# 150219_AriloRX_REV2_0_0.net
KiCad netlist of a schematic drawn in EAGLE
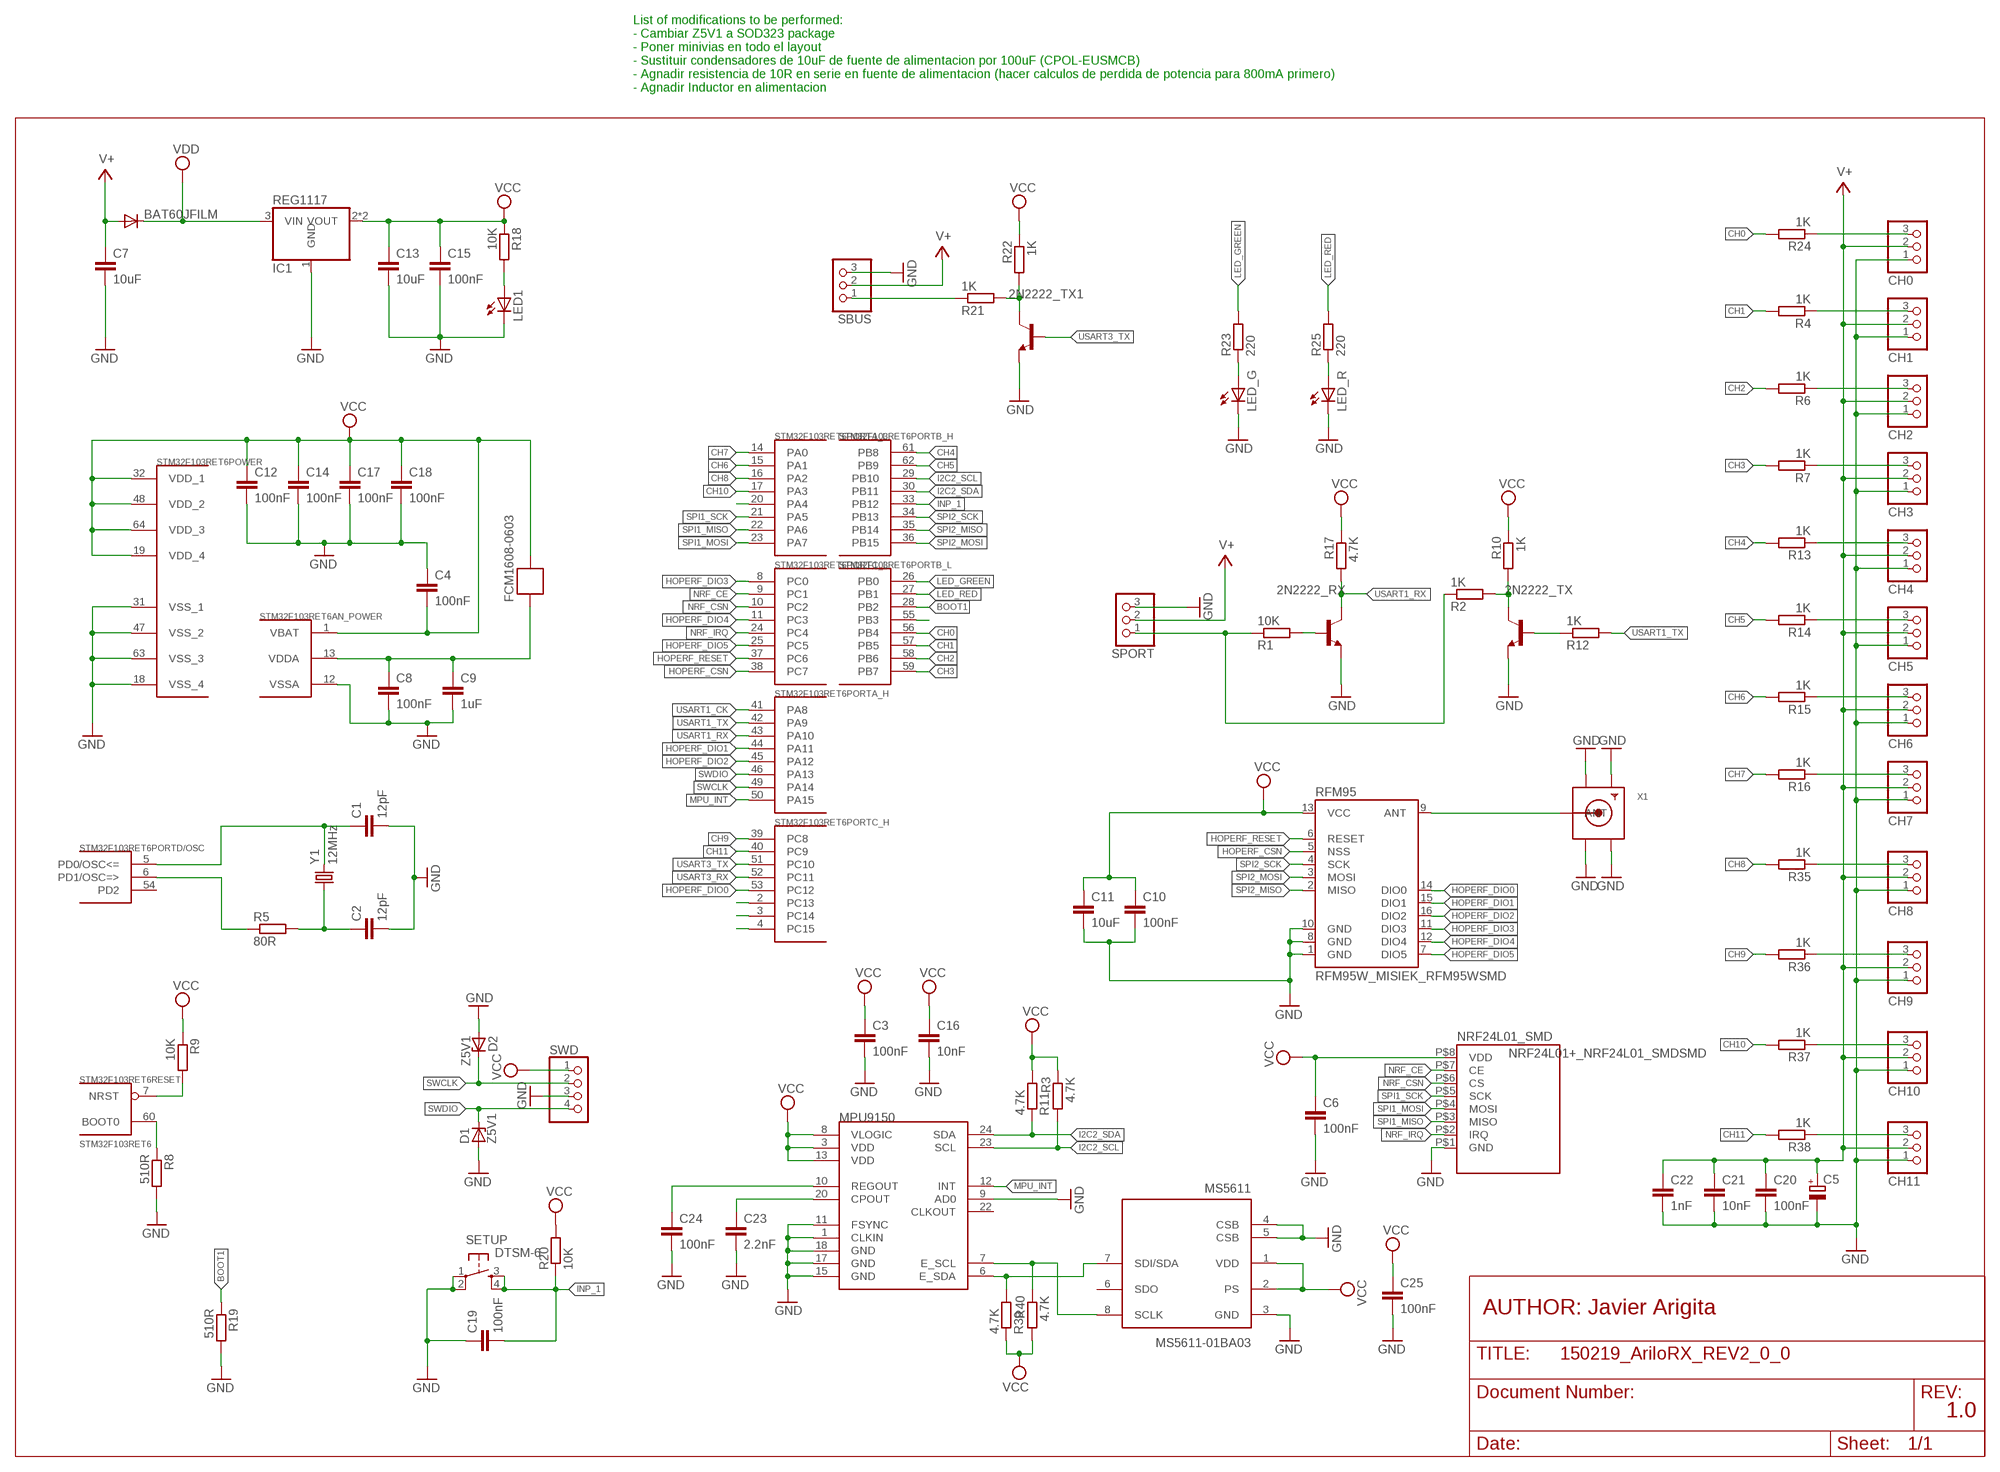
[diagram p0: schematic, sheet 1]

(export (version "E")
  (design (tool "Eeschema 10.0.6"))
  (components
    (comp (ref "2N2222_RX")
      (value "MMBT2222ALT1-NPN-SOT23-BEC")
      (footprint "eagle-import:SOT23-BEC")
      (libsource (lib "eagle-import") (part "-NPN-SOT23-BECMMBT2222ALT1"))
    )
    (comp (ref "2N2222_TX")
      (value "MMBT2222ALT1-NPN-SOT23-BEC")
      (footprint "eagle-import:SOT23-BEC")
      (libsource (lib "eagle-import") (part "-NPN-SOT23-BECMMBT2222ALT1"))
    )
    (comp (ref "2N2222_TX1")
      (value "MMBT2222ALT1-NPN-SOT23-BEC")
      (footprint "eagle-import:SOT23-BEC")
      (libsource (lib "eagle-import") (part "-NPN-SOT23-BECMMBT2222ALT1"))
    )
    (comp (ref "BAT60JFILM")
      (value "DIODE-SOD323-R")
      (footprint "eagle-import:SOD323-R")
      (libsource (lib "eagle-import") (part "DIODE-SOD323-R"))
    )
    (comp (ref "C1")
      (value "12pF")
      (footprint "eagle-import:RESISTOR_C0603")
      (libsource (lib "eagle-import") (part "RESISTOR_C-EUC0603"))
    )
    (comp (ref "C2")
      (value "12pF")
      (footprint "eagle-import:RESISTOR_C0603")
      (libsource (lib "eagle-import") (part "RESISTOR_C-EUC0603"))
    )
    (comp (ref "C3")
      (value "100nF")
      (footprint "eagle-import:RESISTOR_C0603")
      (libsource (lib "eagle-import") (part "RESISTOR_C-EUC0603"))
    )
    (comp (ref "C4")
      (value "100nF")
      (footprint "eagle-import:RESISTOR_C0603")
      (libsource (lib "eagle-import") (part "RESISTOR_C-EUC0603"))
    )
    (comp (ref "C5")
      (value "CPOL-EUSMCB")
      (footprint "eagle-import:SMC_B")
      (libsource (lib "eagle-import") (part "CPOL-EUSMCB"))
    )
    (comp (ref "C6")
      (value "100nF")
      (footprint "eagle-import:RESISTOR_C0603")
      (libsource (lib "eagle-import") (part "RESISTOR_C-EUC0603"))
    )
    (comp (ref "C7")
      (value "10uF")
      (footprint "eagle-import:RESISTOR_C3216")
      (libsource (lib "eagle-import") (part "RESISTOR_C-EUC3216"))
    )
    (comp (ref "C8")
      (value "100nF")
      (footprint "eagle-import:RESISTOR_C0603")
      (libsource (lib "eagle-import") (part "RESISTOR_C-EUC0603"))
    )
    (comp (ref "C9")
      (value "1uF")
      (footprint "eagle-import:RESISTOR_C0603")
      (libsource (lib "eagle-import") (part "RESISTOR_C-EUC0603"))
    )
    (comp (ref "C10")
      (value "100nF")
      (footprint "eagle-import:RESISTOR_C0603")
      (libsource (lib "eagle-import") (part "RESISTOR_C-EUC0603"))
    )
    (comp (ref "C11")
      (value "10uF")
      (footprint "eagle-import:RESISTOR_C3216")
      (libsource (lib "eagle-import") (part "RESISTOR_C-EUC3216"))
    )
    (comp (ref "C12")
      (value "100nF")
      (footprint "eagle-import:RESISTOR_C0603")
      (libsource (lib "eagle-import") (part "RESISTOR_C-EUC0603"))
    )
    (comp (ref "C13")
      (value "10uF")
      (footprint "eagle-import:RESISTOR_C3216")
      (libsource (lib "eagle-import") (part "RESISTOR_C-EUC3216"))
    )
    (comp (ref "C14")
      (value "100nF")
      (footprint "eagle-import:RESISTOR_C0603")
      (libsource (lib "eagle-import") (part "RESISTOR_C-EUC0603"))
    )
    (comp (ref "C15")
      (value "100nF")
      (footprint "eagle-import:RESISTOR_C0603")
      (libsource (lib "eagle-import") (part "RESISTOR_C-EUC0603"))
    )
    (comp (ref "C16")
      (value "10nF")
      (footprint "eagle-import:RESISTOR_C0603")
      (libsource (lib "eagle-import") (part "RESISTOR_C-EUC0603"))
    )
    (comp (ref "C17")
      (value "100nF")
      (footprint "eagle-import:RESISTOR_C0603")
      (libsource (lib "eagle-import") (part "RESISTOR_C-EUC0603"))
    )
    (comp (ref "C18")
      (value "100nF")
      (footprint "eagle-import:RESISTOR_C0603")
      (libsource (lib "eagle-import") (part "RESISTOR_C-EUC0603"))
    )
    (comp (ref "C19")
      (value "100nF")
      (footprint "eagle-import:RESISTOR_C0603")
      (libsource (lib "eagle-import") (part "RESISTOR_C-EUC0603"))
    )
    (comp (ref "C20")
      (value "100nF")
      (footprint "eagle-import:RESISTOR_C0603")
      (libsource (lib "eagle-import") (part "RESISTOR_C-EUC0603"))
    )
    (comp (ref "C21")
      (value "10nF")
      (footprint "eagle-import:RESISTOR_C0603")
      (libsource (lib "eagle-import") (part "RESISTOR_C-EUC0603"))
    )
    (comp (ref "C22")
      (value "1nF")
      (footprint "eagle-import:RESISTOR_C0603")
      (libsource (lib "eagle-import") (part "RESISTOR_C-EUC0603"))
    )
    (comp (ref "C23")
      (value "2.2nF")
      (footprint "eagle-import:RESISTOR_C0603")
      (libsource (lib "eagle-import") (part "RESISTOR_C-EUC0603"))
    )
    (comp (ref "C24")
      (value "100nF")
      (footprint "eagle-import:RESISTOR_C0603")
      (libsource (lib "eagle-import") (part "RESISTOR_C-EUC0603"))
    )
    (comp (ref "C25")
      (value "100nF")
      (footprint "eagle-import:RESISTOR_C0603")
      (libsource (lib "eagle-import") (part "RESISTOR_C-EUC0603"))
    )
    (comp (ref "CH0")
      (value "PINHD-1X3")
      (footprint "eagle-import:1X03")
      (libsource (lib "eagle-import") (part "PINHD-1X3"))
    )
    (comp (ref "CH1")
      (value "PINHD-1X3")
      (footprint "eagle-import:1X03")
      (libsource (lib "eagle-import") (part "PINHD-1X3"))
    )
    (comp (ref "CH2")
      (value "PINHD-1X3")
      (footprint "eagle-import:1X03")
      (libsource (lib "eagle-import") (part "PINHD-1X3"))
    )
    (comp (ref "CH3")
      (value "PINHD-1X3")
      (footprint "eagle-import:1X03")
      (libsource (lib "eagle-import") (part "PINHD-1X3"))
    )
    (comp (ref "CH4")
      (value "PINHD-1X3")
      (footprint "eagle-import:1X03")
      (libsource (lib "eagle-import") (part "PINHD-1X3"))
    )
    (comp (ref "CH5")
      (value "PINHD-1X3")
      (footprint "eagle-import:1X03")
      (libsource (lib "eagle-import") (part "PINHD-1X3"))
    )
    (comp (ref "CH6")
      (value "PINHD-1X3")
      (footprint "eagle-import:1X03")
      (libsource (lib "eagle-import") (part "PINHD-1X3"))
    )
    (comp (ref "CH7")
      (value "PINHD-1X3")
      (footprint "eagle-import:1X03")
      (libsource (lib "eagle-import") (part "PINHD-1X3"))
    )
    (comp (ref "CH8")
      (value "PINHD-1X3")
      (footprint "eagle-import:1X03")
      (libsource (lib "eagle-import") (part "PINHD-1X3"))
    )
    (comp (ref "CH9")
      (value "PINHD-1X3")
      (footprint "eagle-import:1X03")
      (libsource (lib "eagle-import") (part "PINHD-1X3"))
    )
    (comp (ref "CH10")
      (value "PINHD-1X3")
      (footprint "eagle-import:1X03")
      (libsource (lib "eagle-import") (part "PINHD-1X3"))
    )
    (comp (ref "CH11")
      (value "PINHD-1X3")
      (footprint "eagle-import:1X03")
      (libsource (lib "eagle-import") (part "PINHD-1X3"))
    )
    (comp (ref "D1")
      (value "Z5V1")
      (footprint "eagle-import:SOD80C")
      (libsource (lib "eagle-import") (part "ZENER-DIODESOD80C"))
    )
    (comp (ref "D2")
      (value "Z5V1")
      (footprint "eagle-import:SOD80C")
      (libsource (lib "eagle-import") (part "ZENER-DIODESOD80C"))
    )
    (comp (ref "FCM1608-0603")
      (value "FERRITE-BEAD")
      (footprint "eagle-import:R0603")
      (libsource (lib "eagle-import") (part "FERRITE-BEAD"))
    )
    (comp (ref "IC1")
      (value "REG1117")
      (footprint "eagle-import:SOT223")
      (libsource (lib "eagle-import") (part "REG1117"))
    )
    (comp (ref "LED1")
      (value "LED_LEDCHIP-LED0603")
      (footprint "eagle-import:LED_CHIP-LED0603")
      (libsource (lib "eagle-import") (part "LED_LEDCHIP-LED0603"))
    )
    (comp (ref "LED_G")
      (value "LEDCHIP-LED0603")
      (footprint "eagle-import:CHIP-LED0603")
      (libsource (lib "eagle-import") (part "LEDCHIP-LED0603"))
    )
    (comp (ref "LED_R")
      (value "LEDCHIP-LED0603")
      (footprint "eagle-import:CHIP-LED0603")
      (libsource (lib "eagle-import") (part "LEDCHIP-LED0603"))
    )
    (comp (ref "MPU9150")
      (value "MPU-9150QFN-24-NP")
      (footprint "eagle-import:QFN-24-NP")
      (libsource (lib "eagle-import") (part "MPU-9150QFN-24-NP"))
    )
    (comp (ref "MS5611")
      (value "MS5611-01BA03")
      (footprint "eagle-import:SON125P300X500X100-8N")
      (libsource (lib "eagle-import") (part "MS5611-01BA03"))
    )
    (comp (ref "NRF24L01_SMD")
      (value "NRF24L01+_NRF24L01_SMDSMD")
      (footprint "eagle-import:NRF24L01+_NRF24L01_SMD")
      (libsource (lib "eagle-import") (part "NRF24L01+_NRF24L01_SMDSMD"))
    )
    (comp (ref "R1")
      (value "10K")
      (footprint "eagle-import:RCL_R0603")
      (libsource (lib "eagle-import") (part "RCL_R-EU_R0603"))
    )
    (comp (ref "R2")
      (value "1K")
      (footprint "eagle-import:RCL_R0603")
      (libsource (lib "eagle-import") (part "RCL_R-EU_R0603"))
    )
    (comp (ref "R3")
      (value "4.7K")
      (footprint "eagle-import:RCL_R0603")
      (libsource (lib "eagle-import") (part "RCL_R-EU_R0603"))
    )
    (comp (ref "R4")
      (value "1K")
      (footprint "eagle-import:RCL_R0603")
      (libsource (lib "eagle-import") (part "RCL_R-EU_R0603"))
    )
    (comp (ref "R5")
      (value "80R")
      (footprint "eagle-import:RCL_R0603")
      (libsource (lib "eagle-import") (part "RCL_R-EU_R0603"))
    )
    (comp (ref "R6")
      (value "1K")
      (footprint "eagle-import:RCL_R0603")
      (libsource (lib "eagle-import") (part "RCL_R-EU_R0603"))
    )
    (comp (ref "R7")
      (value "1K")
      (footprint "eagle-import:RCL_R0603")
      (libsource (lib "eagle-import") (part "RCL_R-EU_R0603"))
    )
    (comp (ref "R8")
      (value "510R")
      (footprint "eagle-import:RCL_R0603")
      (libsource (lib "eagle-import") (part "RCL_R-EU_R0603"))
    )
    (comp (ref "R9")
      (value "10K")
      (footprint "eagle-import:RCL_R0603")
      (libsource (lib "eagle-import") (part "RCL_R-EU_R0603"))
    )
    (comp (ref "R10")
      (value "1K")
      (footprint "eagle-import:RCL_R0603")
      (libsource (lib "eagle-import") (part "RCL_R-EU_R0603"))
    )
    (comp (ref "R11")
      (value "4.7K")
      (footprint "eagle-import:RCL_R0603")
      (libsource (lib "eagle-import") (part "RCL_R-EU_R0603"))
    )
    (comp (ref "R12")
      (value "1K")
      (footprint "eagle-import:RCL_R0603")
      (libsource (lib "eagle-import") (part "RCL_R-EU_R0603"))
    )
    (comp (ref "R13")
      (value "1K")
      (footprint "eagle-import:RCL_R0603")
      (libsource (lib "eagle-import") (part "RCL_R-EU_R0603"))
    )
    (comp (ref "R14")
      (value "1K")
      (footprint "eagle-import:RCL_R0603")
      (libsource (lib "eagle-import") (part "RCL_R-EU_R0603"))
    )
    (comp (ref "R15")
      (value "1K")
      (footprint "eagle-import:RCL_R0603")
      (libsource (lib "eagle-import") (part "RCL_R-EU_R0603"))
    )
    (comp (ref "R16")
      (value "1K")
      (footprint "eagle-import:RCL_R0603")
      (libsource (lib "eagle-import") (part "RCL_R-EU_R0603"))
    )
    (comp (ref "R17")
      (value "4.7K")
      (footprint "eagle-import:RCL_R0603")
      (libsource (lib "eagle-import") (part "RCL_R-EU_R0603"))
    )
    (comp (ref "R18")
      (value "10K")
      (footprint "eagle-import:RCL_R0603")
      (libsource (lib "eagle-import") (part "RCL_R-EU_R0603"))
    )
    (comp (ref "R19")
      (value "510R")
      (footprint "eagle-import:RCL_R0603")
      (libsource (lib "eagle-import") (part "RCL_R-EU_R0603"))
    )
    (comp (ref "R20")
      (value "10K")
      (footprint "eagle-import:RCL_R0603")
      (libsource (lib "eagle-import") (part "RCL_R-EU_R0603"))
    )
    (comp (ref "R21")
      (value "1K")
      (footprint "eagle-import:RCL_R0603")
      (libsource (lib "eagle-import") (part "RCL_R-EU_R0603"))
    )
    (comp (ref "R22")
      (value "1K")
      (footprint "eagle-import:RCL_R0603")
      (libsource (lib "eagle-import") (part "RCL_R-EU_R0603"))
    )
    (comp (ref "R23")
      (value "220")
      (footprint "eagle-import:RCL_R0603")
      (libsource (lib "eagle-import") (part "RCL_R-EU_R0603"))
    )
    (comp (ref "R24")
      (value "1K")
      (footprint "eagle-import:RCL_R0603")
      (libsource (lib "eagle-import") (part "RCL_R-EU_R0603"))
    )
    (comp (ref "R25")
      (value "220")
      (footprint "eagle-import:RCL_R0603")
      (libsource (lib "eagle-import") (part "RCL_R-EU_R0603"))
    )
    (comp (ref "R35")
      (value "1K")
      (footprint "eagle-import:RCL_R0603")
      (libsource (lib "eagle-import") (part "RCL_R-EU_R0603"))
    )
    (comp (ref "R36")
      (value "1K")
      (footprint "eagle-import:RCL_R0603")
      (libsource (lib "eagle-import") (part "RCL_R-EU_R0603"))
    )
    (comp (ref "R37")
      (value "1K")
      (footprint "eagle-import:RCL_R0603")
      (libsource (lib "eagle-import") (part "RCL_R-EU_R0603"))
    )
    (comp (ref "R38")
      (value "1K")
      (footprint "eagle-import:RCL_R0603")
      (libsource (lib "eagle-import") (part "RCL_R-EU_R0603"))
    )
    (comp (ref "R39")
      (value "4.7K")
      (footprint "eagle-import:RCL_R0603")
      (libsource (lib "eagle-import") (part "RCL_R-EU_R0603"))
    )
    (comp (ref "R40")
      (value "4.7K")
      (footprint "eagle-import:RCL_R0603")
      (libsource (lib "eagle-import") (part "RCL_R-EU_R0603"))
    )
    (comp (ref "RFM95")
      (value "RFM95W_MISIEK_RFM95WSMD")
      (footprint "eagle-import:RFM95W_MISIEK_RFM95W_SMD")
      (libsource (lib "eagle-import") (part "RFM95W_MISIEK_RFM95WSMD"))
    )
    (comp (ref "SBUS")
      (value "PINHD-1X3")
      (footprint "eagle-import:1X03")
      (libsource (lib "eagle-import") (part "PINHD-1X3"))
    )
    (comp (ref "SETUP")
      (value "DTSM-6")
      (footprint "eagle-import:DTSM-6")
      (libsource (lib "eagle-import") (part "DTSM-6"))
    )
    (comp (ref "SPORT")
      (value "PINHD-1X3")
      (footprint "eagle-import:1X03")
      (libsource (lib "eagle-import") (part "PINHD-1X3"))
    )
    (comp (ref "STM32F103RET6")
      (value "STM32F103RET6")
      (footprint "eagle-import:TQFP64")
      (libsource (lib "eagle-import") (part "STM32F10XRXT6"))
    )
    (comp (ref "SWD")
      (value "PINHD-1X4")
      (footprint "eagle-import:1X04")
      (libsource (lib "eagle-import") (part "PINHD-1X4"))
    )
    (comp (ref "X1")
      (value "SMACONNECTOR_EDGE")
      (footprint "eagle-import:SMA_EDGELAUNCH")
      (libsource (lib "eagle-import") (part "SMACONNECTOR_EDGE"))
    )
    (comp (ref "Y1")
      (value "12MHz")
      (footprint "eagle-import:CRYSTAL-SMD-5X3")
      (libsource (lib "eagle-import") (part "CRYSTAL5X3"))
    )
  )
  (nets
    (net (code "1") (name "BOOT1") (class "Default")
      (node (ref "R19") (pin "1") (pinfunction "1_1") (pintype "passive"))
      (node (ref "STM32F103RET6") (pin "28") (pinfunction "PB2_28") (pintype "bidirectional"))
    )
    (net (code "2") (name "CH0") (class "Default")
      (node (ref "R24") (pin "2") (pinfunction "2_2") (pintype "passive"))
      (node (ref "STM32F103RET6") (pin "56") (pinfunction "PB4_56") (pintype "bidirectional"))
    )
    (net (code "3") (name "CH1") (class "Default")
      (node (ref "R4") (pin "2") (pinfunction "2_2") (pintype "passive"))
      (node (ref "STM32F103RET6") (pin "57") (pinfunction "PB5_57") (pintype "bidirectional"))
    )
    (net (code "4") (name "CH2") (class "Default")
      (node (ref "R6") (pin "2") (pinfunction "2_2") (pintype "passive"))
      (node (ref "STM32F103RET6") (pin "58") (pinfunction "PB6_58") (pintype "bidirectional"))
    )
    (net (code "5") (name "CH3") (class "Default")
      (node (ref "R7") (pin "2") (pinfunction "2_2") (pintype "passive"))
      (node (ref "STM32F103RET6") (pin "59") (pinfunction "PB7_59") (pintype "bidirectional"))
    )
    (net (code "6") (name "CH4") (class "Default")
      (node (ref "R13") (pin "2") (pinfunction "2_2") (pintype "passive"))
      (node (ref "STM32F103RET6") (pin "61") (pinfunction "PB8_61") (pintype "bidirectional"))
    )
    (net (code "7") (name "CH5") (class "Default")
      (node (ref "R14") (pin "2") (pinfunction "2_2") (pintype "passive"))
      (node (ref "STM32F103RET6") (pin "62") (pinfunction "PB9_62") (pintype "bidirectional"))
    )
    (net (code "8") (name "CH6") (class "Default")
      (node (ref "R15") (pin "2") (pinfunction "2_2") (pintype "passive"))
      (node (ref "STM32F103RET6") (pin "15") (pinfunction "PA1_15") (pintype "bidirectional"))
    )
    (net (code "9") (name "CH7") (class "Default")
      (node (ref "R16") (pin "2") (pinfunction "2_2") (pintype "passive"))
      (node (ref "STM32F103RET6") (pin "14") (pinfunction "PA0_14") (pintype "bidirectional"))
    )
    (net (code "10") (name "CH8") (class "Default")
      (node (ref "R35") (pin "2") (pinfunction "2_2") (pintype "passive"))
      (node (ref "STM32F103RET6") (pin "16") (pinfunction "PA2_16") (pintype "bidirectional"))
    )
    (net (code "11") (name "CH9") (class "Default")
      (node (ref "R36") (pin "2") (pinfunction "2_2") (pintype "passive"))
      (node (ref "STM32F103RET6") (pin "39") (pinfunction "PC8_39") (pintype "bidirectional"))
    )
    (net (code "12") (name "CH10") (class "Default")
      (node (ref "R37") (pin "2") (pinfunction "2_2") (pintype "passive"))
      (node (ref "STM32F103RET6") (pin "17") (pinfunction "PA3_17") (pintype "bidirectional"))
    )
    (net (code "13") (name "CH11") (class "Default")
      (node (ref "R38") (pin "2") (pinfunction "2_2") (pintype "passive"))
      (node (ref "STM32F103RET6") (pin "40") (pinfunction "PC9_40") (pintype "bidirectional"))
    )
    (net (code "14") (name "GND") (class "Default")
      (node (ref "2N2222_RX") (pin "E") (pinfunction "E_E") (pintype "passive"))
      (node (ref "2N2222_TX") (pin "E") (pinfunction "E_E") (pintype "passive"))
      (node (ref "2N2222_TX1") (pin "E") (pinfunction "E_E") (pintype "passive"))
      (node (ref "C1") (pin "2") (pinfunction "2_2") (pintype "passive"))
      (node (ref "C10") (pin "2") (pinfunction "2_2") (pintype "passive"))
      (node (ref "C11") (pin "2") (pinfunction "2_2") (pintype "passive"))
      (node (ref "C12") (pin "2") (pinfunction "2_2") (pintype "passive"))
      (node (ref "C13") (pin "2") (pinfunction "2_2") (pintype "passive"))
      (node (ref "C14") (pin "2") (pinfunction "2_2") (pintype "passive"))
      (node (ref "C15") (pin "2") (pinfunction "2_2") (pintype "passive"))
      (node (ref "C16") (pin "2") (pinfunction "2_2") (pintype "passive"))
      (node (ref "C17") (pin "2") (pinfunction "2_2") (pintype "passive"))
      (node (ref "C18") (pin "2") (pinfunction "2_2") (pintype "passive"))
      (node (ref "C19") (pin "1") (pinfunction "1_1") (pintype "passive"))
      (node (ref "C2") (pin "2") (pinfunction "2_2") (pintype "passive"))
      (node (ref "C20") (pin "2") (pinfunction "2_2") (pintype "passive"))
      (node (ref "C21") (pin "2") (pinfunction "2_2") (pintype "passive"))
      (node (ref "C22") (pin "2") (pinfunction "2_2") (pintype "passive"))
      (node (ref "C23") (pin "2") (pinfunction "2_2") (pintype "passive"))
      (node (ref "C24") (pin "2") (pinfunction "2_2") (pintype "passive"))
      (node (ref "C25") (pin "2") (pinfunction "2_2") (pintype "passive"))
      (node (ref "C3") (pin "2") (pinfunction "2_2") (pintype "passive"))
      (node (ref "C4") (pin "1") (pinfunction "1_1") (pintype "passive"))
      (node (ref "C5") (pin "-") (pinfunction "-_-") (pintype "passive"))
      (node (ref "C6") (pin "2") (pinfunction "2_2") (pintype "passive"))
      (node (ref "C7") (pin "2") (pinfunction "2_2") (pintype "passive"))
      (node (ref "C8") (pin "2") (pinfunction "2_2") (pintype "passive"))
      (node (ref "C9") (pin "2") (pinfunction "2_2") (pintype "passive"))
      (node (ref "CH0") (pin "1") (pinfunction "1_1") (pintype "passive"))
      (node (ref "CH1") (pin "1") (pinfunction "1_1") (pintype "passive"))
      (node (ref "CH10") (pin "1") (pinfunction "1_1") (pintype "passive"))
      (node (ref "CH11") (pin "1") (pinfunction "1_1") (pintype "passive"))
      (node (ref "CH2") (pin "1") (pinfunction "1_1") (pintype "passive"))
      (node (ref "CH3") (pin "1") (pinfunction "1_1") (pintype "passive"))
      (node (ref "CH4") (pin "1") (pinfunction "1_1") (pintype "passive"))
      (node (ref "CH5") (pin "1") (pinfunction "1_1") (pintype "passive"))
      (node (ref "CH6") (pin "1") (pinfunction "1_1") (pintype "passive"))
      (node (ref "CH7") (pin "1") (pinfunction "1_1") (pintype "passive"))
      (node (ref "CH8") (pin "1") (pinfunction "1_1") (pintype "passive"))
      (node (ref "CH9") (pin "1") (pinfunction "1_1") (pintype "passive"))
      (node (ref "D1") (pin "A") (pinfunction "A_A") (pintype "passive"))
      (node (ref "D2") (pin "A") (pinfunction "A_A") (pintype "passive"))
      (node (ref "IC1") (pin "1") (pinfunction "GND_1") (pintype "power_in"))
      (node (ref "LED1") (pin "C") (pinfunction "C_C") (pintype "passive"))
      (node (ref "LED_G") (pin "C") (pinfunction "C_C") (pintype "passive"))
      (node (ref "LED_R") (pin "C") (pinfunction "C_C") (pintype "passive"))
      (node (ref "MPU9150") (pin "1") (pinfunction "CLKIN_1") (pintype "bidirectional"))
      (node (ref "MPU9150") (pin "11") (pinfunction "FSYNC_11") (pintype "bidirectional"))
      (node (ref "MPU9150") (pin "15") (pinfunction "GND_15") (pintype "bidirectional"))
      (node (ref "MPU9150") (pin "17") (pinfunction "GND_17") (pintype "bidirectional"))
      (node (ref "MPU9150") (pin "18") (pinfunction "GND_18") (pintype "bidirectional"))
      (node (ref "MPU9150") (pin "9") (pinfunction "AD0_9") (pintype "bidirectional"))
      (node (ref "MS5611") (pin "3") (pinfunction "GND_3") (pintype "power_in"))
      (node (ref "MS5611") (pin "4") (pinfunction "CSB_4") (pintype "input"))
      (node (ref "MS5611") (pin "5") (pinfunction "CSB_5") (pintype "input"))
      (node (ref "NRF24L01_SMD") (pin "P$1") (pinfunction "GND_P$1") (pintype "power_in"))
      (node (ref "R19") (pin "2") (pinfunction "2_2") (pintype "passive"))
      (node (ref "R8") (pin "2") (pinfunction "2_2") (pintype "passive"))
      (node (ref "RFM95") (pin "1") (pinfunction "GND_1") (pintype "power_in"))
      (node (ref "RFM95") (pin "10") (pinfunction "GND_10") (pintype "power_in"))
      (node (ref "RFM95") (pin "8") (pinfunction "GND_8") (pintype "power_in"))
      (node (ref "SBUS") (pin "3") (pinfunction "3_3") (pintype "passive"))
      (node (ref "SETUP") (pin "1") (pinfunction "1_1") (pintype "passive"))
      (node (ref "SETUP") (pin "2") (pinfunction "2_2") (pintype "passive"))
      (node (ref "SPORT") (pin "3") (pinfunction "3_3") (pintype "passive"))
      (node (ref "STM32F103RET6") (pin "12") (pinfunction "VSSA_12") (pintype "power_in"))
      (node (ref "STM32F103RET6") (pin "18") (pinfunction "VSS_4_18") (pintype "power_in"))
      (node (ref "STM32F103RET6") (pin "31") (pinfunction "VSS_1_31") (pintype "power_in"))
      (node (ref "STM32F103RET6") (pin "47") (pinfunction "VSS_2_47") (pintype "power_in"))
      (node (ref "STM32F103RET6") (pin "63") (pinfunction "VSS_3_63") (pintype "power_in"))
      (node (ref "SWD") (pin "3") (pinfunction "3_3") (pintype "passive"))
      (node (ref "X1") (pin "GND@1") (pinfunction "GND4_GND@1") (pintype "power_in"))
      (node (ref "X1") (pin "GND@2") (pinfunction "GND3_GND@2") (pintype "power_in"))
      (node (ref "X1") (pin "GND@3") (pinfunction "GND2_GND@3") (pintype "power_in"))
      (node (ref "X1") (pin "GND@4") (pinfunction "GND1_GND@4") (pintype "power_in"))
    )
    (net (code "15") (name "HOPERF_CSN") (class "Default")
      (node (ref "RFM95") (pin "5") (pinfunction "NSS_5") (pintype "input"))
      (node (ref "STM32F103RET6") (pin "38") (pinfunction "PC7_38") (pintype "bidirectional"))
    )
    (net (code "16") (name "HOPERF_DIO0") (class "Default")
      (node (ref "RFM95") (pin "14") (pinfunction "DIO0_14") (pintype "input"))
      (node (ref "STM32F103RET6") (pin "53") (pinfunction "PC12_53") (pintype "bidirectional"))
    )
    (net (code "17") (name "HOPERF_DIO1") (class "Default")
      (node (ref "RFM95") (pin "15") (pinfunction "DIO1_15") (pintype "input"))
      (node (ref "STM32F103RET6") (pin "44") (pinfunction "PA11_44") (pintype "bidirectional"))
    )
    (net (code "18") (name "HOPERF_DIO2") (class "Default")
      (node (ref "RFM95") (pin "16") (pinfunction "DIO2_16") (pintype "input"))
      (node (ref "STM32F103RET6") (pin "45") (pinfunction "PA12_45") (pintype "bidirectional"))
    )
    (net (code "19") (name "HOPERF_DIO3") (class "Default")
      (node (ref "RFM95") (pin "11") (pinfunction "DIO3_11") (pintype "bidirectional"))
      (node (ref "STM32F103RET6") (pin "8") (pinfunction "PC0_8") (pintype "bidirectional"))
    )
    (net (code "20") (name "HOPERF_DIO4") (class "Default")
      (node (ref "RFM95") (pin "12") (pinfunction "DIO4_12") (pintype "bidirectional"))
      (node (ref "STM32F103RET6") (pin "11") (pinfunction "PC3_11") (pintype "bidirectional"))
    )
    (net (code "21") (name "HOPERF_DIO5") (class "Default")
      (node (ref "RFM95") (pin "7") (pinfunction "DIO5_7") (pintype "bidirectional"))
      (node (ref "STM32F103RET6") (pin "25") (pinfunction "PC5_25") (pintype "bidirectional"))
    )
    (net (code "22") (name "HOPERF_RESET") (class "Default")
      (node (ref "RFM95") (pin "6") (pinfunction "RESET_6") (pintype "output"))
      (node (ref "STM32F103RET6") (pin "37") (pinfunction "PC6_37") (pintype "bidirectional"))
    )
    (net (code "23") (name "I2C2_SCL") (class "Default")
      (node (ref "MPU9150") (pin "23") (pinfunction "SCL_23") (pintype "bidirectional"))
      (node (ref "R3") (pin "2") (pinfunction "2_2") (pintype "passive"))
      (node (ref "STM32F103RET6") (pin "29") (pinfunction "PB10_29") (pintype "bidirectional"))
    )
    (net (code "24") (name "I2C2_SDA") (class "Default")
      (node (ref "MPU9150") (pin "24") (pinfunction "SDA_24") (pintype "bidirectional"))
      (node (ref "R11") (pin "1") (pinfunction "1_1") (pintype "passive"))
      (node (ref "STM32F103RET6") (pin "30") (pinfunction "PB11_30") (pintype "bidirectional"))
    )
    (net (code "25") (name "INP_1") (class "Default")
      (node (ref "C19") (pin "2") (pinfunction "2_2") (pintype "passive"))
      (node (ref "R20") (pin "1") (pinfunction "1_1") (pintype "passive"))
      (node (ref "SETUP") (pin "3") (pinfunction "3_3") (pintype "passive"))
      (node (ref "SETUP") (pin "4") (pinfunction "4_4") (pintype "passive"))
      (node (ref "STM32F103RET6") (pin "33") (pinfunction "PB12_33") (pintype "bidirectional"))
    )
    (net (code "26") (name "LED_GREEN") (class "Default")
      (node (ref "R23") (pin "2") (pinfunction "2_2") (pintype "passive"))
      (node (ref "STM32F103RET6") (pin "26") (pinfunction "PB0_26") (pintype "bidirectional"))
    )
    (net (code "27") (name "LED_RED") (class "Default")
      (node (ref "R25") (pin "2") (pinfunction "2_2") (pintype "passive"))
      (node (ref "STM32F103RET6") (pin "27") (pinfunction "PB1_27") (pintype "bidirectional"))
    )
    (net (code "28") (name "MPU_INT") (class "Default")
      (node (ref "MPU9150") (pin "12") (pinfunction "INT_12") (pintype "bidirectional"))
      (node (ref "STM32F103RET6") (pin "50") (pinfunction "PA15_50") (pintype "bidirectional"))
    )
    (net (code "29") (name "NRF_CE") (class "Default")
      (node (ref "NRF24L01_SMD") (pin "P$7") (pinfunction "CE_P$7") (pintype "input"))
      (node (ref "STM32F103RET6") (pin "9") (pinfunction "PC1_9") (pintype "bidirectional"))
    )
    (net (code "30") (name "NRF_CSN") (class "Default")
      (node (ref "NRF24L01_SMD") (pin "P$6") (pinfunction "CS_P$6") (pintype "input"))
      (node (ref "STM32F103RET6") (pin "10") (pinfunction "PC2_10") (pintype "bidirectional"))
    )
    (net (code "31") (name "NRF_IRQ") (class "Default")
      (node (ref "NRF24L01_SMD") (pin "P$2") (pinfunction "IRQ_P$2") (pintype "output"))
      (node (ref "STM32F103RET6") (pin "24") (pinfunction "PC4_24") (pintype "bidirectional"))
    )
    (net (code "32") (name "Net-(2N2222_RX-PadB)") (class "Default")
      (node (ref "2N2222_RX") (pin "B") (pinfunction "B_B") (pintype "passive"))
      (node (ref "R1") (pin "2") (pinfunction "2_2") (pintype "passive"))
    )
    (net (code "33") (name "Net-(2N2222_TX-PadB)") (class "Default")
      (node (ref "2N2222_TX") (pin "B") (pinfunction "B_B") (pintype "passive"))
      (node (ref "R12") (pin "1") (pinfunction "1_1") (pintype "passive"))
    )
    (net (code "34") (name "Net-(2N2222_TX-PadC)") (class "Default")
      (node (ref "2N2222_TX") (pin "C") (pinfunction "C_C") (pintype "passive"))
      (node (ref "R10") (pin "2") (pinfunction "2_2") (pintype "passive"))
      (node (ref "R2") (pin "2") (pinfunction "2_2") (pintype "passive"))
    )
    (net (code "35") (name "Net-(2N2222_TX1-PadC)") (class "Default")
      (node (ref "2N2222_TX1") (pin "C") (pinfunction "C_C") (pintype "passive"))
      (node (ref "R21") (pin "2") (pinfunction "2_2") (pintype "passive"))
      (node (ref "R22") (pin "2") (pinfunction "2_2") (pintype "passive"))
    )
    (net (code "36") (name "Net-(C2-Pad1)") (class "Default")
      (node (ref "C2") (pin "1") (pinfunction "1_1") (pintype "passive"))
      (node (ref "R5") (pin "2") (pinfunction "2_2") (pintype "passive"))
      (node (ref "Y1") (pin "1") (pinfunction "1_1") (pintype "passive"))
    )
    (net (code "37") (name "Net-(CH0-Pad3)") (class "Default")
      (node (ref "CH0") (pin "3") (pinfunction "3_3") (pintype "passive"))
      (node (ref "R24") (pin "1") (pinfunction "1_1") (pintype "passive"))
    )
    (net (code "38") (name "Net-(CH1-Pad3)") (class "Default")
      (node (ref "CH1") (pin "3") (pinfunction "3_3") (pintype "passive"))
      (node (ref "R4") (pin "1") (pinfunction "1_1") (pintype "passive"))
    )
    (net (code "39") (name "Net-(CH2-Pad3)") (class "Default")
      (node (ref "CH2") (pin "3") (pinfunction "3_3") (pintype "passive"))
      (node (ref "R6") (pin "1") (pinfunction "1_1") (pintype "passive"))
    )
    (net (code "40") (name "Net-(CH3-Pad3)") (class "Default")
      (node (ref "CH3") (pin "3") (pinfunction "3_3") (pintype "passive"))
      (node (ref "R7") (pin "1") (pinfunction "1_1") (pintype "passive"))
    )
    (net (code "41") (name "Net-(CH4-Pad3)") (class "Default")
      (node (ref "CH4") (pin "3") (pinfunction "3_3") (pintype "passive"))
      (node (ref "R13") (pin "1") (pinfunction "1_1") (pintype "passive"))
    )
    (net (code "42") (name "Net-(CH5-Pad3)") (class "Default")
      (node (ref "CH5") (pin "3") (pinfunction "3_3") (pintype "passive"))
      (node (ref "R14") (pin "1") (pinfunction "1_1") (pintype "passive"))
    )
    (net (code "43") (name "Net-(CH6-Pad3)") (class "Default")
      (node (ref "CH6") (pin "3") (pinfunction "3_3") (pintype "passive"))
      (node (ref "R15") (pin "1") (pinfunction "1_1") (pintype "passive"))
    )
    (net (code "44") (name "Net-(CH7-Pad3)") (class "Default")
      (node (ref "CH7") (pin "3") (pinfunction "3_3") (pintype "passive"))
      (node (ref "R16") (pin "1") (pinfunction "1_1") (pintype "passive"))
    )
    (net (code "45") (name "Net-(CH8-Pad3)") (class "Default")
      (node (ref "CH8") (pin "3") (pinfunction "3_3") (pintype "passive"))
      (node (ref "R35") (pin "1") (pinfunction "1_1") (pintype "passive"))
    )
    (net (code "46") (name "Net-(CH9-Pad3)") (class "Default")
      (node (ref "CH9") (pin "3") (pinfunction "3_3") (pintype "passive"))
      (node (ref "R36") (pin "1") (pinfunction "1_1") (pintype "passive"))
    )
    (net (code "47") (name "Net-(CH10-Pad3)") (class "Default")
      (node (ref "CH10") (pin "3") (pinfunction "3_3") (pintype "passive"))
      (node (ref "R37") (pin "1") (pinfunction "1_1") (pintype "passive"))
    )
    (net (code "48") (name "Net-(CH11-Pad3)") (class "Default")
      (node (ref "CH11") (pin "3") (pinfunction "3_3") (pintype "passive"))
      (node (ref "R38") (pin "1") (pinfunction "1_1") (pintype "passive"))
    )
    (net (code "49") (name "Net-(FCM1608-0603-P$2)") (class "Default")
      (node (ref "C8") (pin "1") (pinfunction "1_1") (pintype "passive"))
      (node (ref "C9") (pin "1") (pinfunction "1_1") (pintype "passive"))
      (node (ref "FCM1608-0603") (pin "2") (pinfunction "P$2_2") (pintype "bidirectional"))
      (node (ref "STM32F103RET6") (pin "13") (pinfunction "VDDA_13") (pintype "power_in"))
    )
    (net (code "50") (name "Net-(LED1-PadA)") (class "Default")
      (node (ref "LED1") (pin "A") (pinfunction "A_A") (pintype "passive"))
      (node (ref "R18") (pin "2") (pinfunction "2_2") (pintype "passive"))
    )
    (net (code "51") (name "Net-(LED_G-PadA)") (class "Default")
      (node (ref "LED_G") (pin "A") (pinfunction "A_A") (pintype "passive"))
      (node (ref "R23") (pin "1") (pinfunction "1_1") (pintype "passive"))
    )
    (net (code "52") (name "Net-(LED_R-PadA)") (class "Default")
      (node (ref "LED_R") (pin "A") (pinfunction "A_A") (pintype "passive"))
      (node (ref "R25") (pin "1") (pinfunction "1_1") (pintype "passive"))
    )
    (net (code "53") (name "Net-(MPU9150-CPOUT)") (class "Default")
      (node (ref "C23") (pin "1") (pinfunction "1_1") (pintype "passive"))
      (node (ref "MPU9150") (pin "20") (pinfunction "CPOUT_20") (pintype "bidirectional"))
    )
    (net (code "54") (name "Net-(MPU9150-E_SCL)") (class "Default")
      (node (ref "MPU9150") (pin "7") (pinfunction "E_SCL_7") (pintype "bidirectional"))
      (node (ref "MS5611") (pin "8") (pinfunction "SCLK_8") (pintype "input"))
      (node (ref "R40") (pin "1") (pinfunction "1_1") (pintype "passive"))
    )
    (net (code "55") (name "Net-(MPU9150-E_SDA)") (class "Default")
      (node (ref "MPU9150") (pin "6") (pinfunction "E_SDA_6") (pintype "bidirectional"))
      (node (ref "MS5611") (pin "7") (pinfunction "SDI/SDA_7") (pintype "bidirectional"))
      (node (ref "R39") (pin "2") (pinfunction "2_2") (pintype "passive"))
    )
    (net (code "56") (name "Net-(MPU9150-REGOUT)") (class "Default")
      (node (ref "C24") (pin "1") (pinfunction "1_1") (pintype "passive"))
      (node (ref "MPU9150") (pin "10") (pinfunction "REGOUT_10") (pintype "bidirectional"))
    )
    (net (code "57") (name "Net-(R1-Pad1)") (class "Default")
      (node (ref "R1") (pin "1") (pinfunction "1_1") (pintype "passive"))
      (node (ref "R2") (pin "1") (pinfunction "1_1") (pintype "passive"))
      (node (ref "SPORT") (pin "1") (pinfunction "1_1") (pintype "passive"))
    )
    (net (code "58") (name "Net-(R21-Pad1)") (class "Default")
      (node (ref "R21") (pin "1") (pinfunction "1_1") (pintype "passive"))
      (node (ref "SBUS") (pin "1") (pinfunction "1_1") (pintype "passive"))
    )
    (net (code "59") (name "Net-(RFM95-ANT)") (class "Default")
      (node (ref "RFM95") (pin "9") (pinfunction "ANT_9") (pintype "bidirectional"))
      (node (ref "X1") (pin "P") (pinfunction "ANT_P") (pintype "bidirectional"))
    )
    (net (code "60") (name "Net-(STM32F103RET6H-PD0{slash}OSC<=)") (class "Default")
      (node (ref "C1") (pin "1") (pinfunction "1_1") (pintype "passive"))
      (node (ref "STM32F103RET6") (pin "5") (pinfunction "PD0/OSC<=_5") (pintype "bidirectional"))
      (node (ref "Y1") (pin "3") (pinfunction "2_3") (pintype "passive"))
    )
    (net (code "61") (name "Net-(STM32F103RET6H-PD1{slash}OSC=>)") (class "Default")
      (node (ref "R5") (pin "1") (pinfunction "1_1") (pintype "passive"))
      (node (ref "STM32F103RET6") (pin "6") (pinfunction "PD1/OSC=>_6") (pintype "bidirectional"))
    )
    (net (code "62") (name "Net-(STM32F103RET6J-BOOT0)") (class "Default")
      (node (ref "R8") (pin "1") (pinfunction "1_1") (pintype "passive"))
      (node (ref "STM32F103RET6") (pin "60") (pinfunction "BOOT0_60") (pintype "input"))
    )
    (net (code "63") (name "Net-(STM32F103RET6J-NRST)") (class "Default")
      (node (ref "R9") (pin "2") (pinfunction "2_2") (pintype "passive"))
      (node (ref "STM32F103RET6") (pin "7") (pinfunction "NRST_7") (pintype "input"))
    )
    (net (code "64") (name "SPI1_MISO") (class "Default")
      (node (ref "NRF24L01_SMD") (pin "P$3") (pinfunction "MISO_P$3") (pintype "output"))
      (node (ref "STM32F103RET6") (pin "22") (pinfunction "PA6_22") (pintype "bidirectional"))
    )
    (net (code "65") (name "SPI1_MOSI") (class "Default")
      (node (ref "NRF24L01_SMD") (pin "P$4") (pinfunction "MOSI_P$4") (pintype "input"))
      (node (ref "STM32F103RET6") (pin "23") (pinfunction "PA7_23") (pintype "bidirectional"))
    )
    (net (code "66") (name "SPI1_SCK") (class "Default")
      (node (ref "NRF24L01_SMD") (pin "P$5") (pinfunction "SCK_P$5") (pintype "input"))
      (node (ref "STM32F103RET6") (pin "21") (pinfunction "PA5_21") (pintype "bidirectional"))
    )
    (net (code "67") (name "SPI2_MISO") (class "Default")
      (node (ref "RFM95") (pin "2") (pinfunction "MISO_2") (pintype "output"))
      (node (ref "STM32F103RET6") (pin "35") (pinfunction "PB14_35") (pintype "bidirectional"))
    )
    (net (code "68") (name "SPI2_MOSI") (class "Default")
      (node (ref "RFM95") (pin "3") (pinfunction "MOSI_3") (pintype "input"))
      (node (ref "STM32F103RET6") (pin "36") (pinfunction "PB15_36") (pintype "bidirectional"))
    )
    (net (code "69") (name "SPI2_SCK") (class "Default")
      (node (ref "RFM95") (pin "4") (pinfunction "SCK_4") (pintype "input"))
      (node (ref "STM32F103RET6") (pin "34") (pinfunction "PB13_34") (pintype "bidirectional"))
    )
    (net (code "70") (name "SWCLK") (class "Default")
      (node (ref "D2") (pin "C") (pinfunction "C_C") (pintype "passive"))
      (node (ref "STM32F103RET6") (pin "49") (pinfunction "PA14_49") (pintype "bidirectional"))
      (node (ref "SWD") (pin "2") (pinfunction "2_2") (pintype "passive"))
    )
    (net (code "71") (name "SWDIO") (class "Default")
      (node (ref "D1") (pin "C") (pinfunction "C_C") (pintype "passive"))
      (node (ref "STM32F103RET6") (pin "46") (pinfunction "PA13_46") (pintype "bidirectional"))
      (node (ref "SWD") (pin "4") (pinfunction "4_4") (pintype "passive"))
    )
    (net (code "72") (name "USART1_CK") (class "Default")
      (node (ref "STM32F103RET6") (pin "41") (pinfunction "PA8_41") (pintype "bidirectional"))
    )
    (net (code "73") (name "USART1_RX") (class "Default")
      (node (ref "2N2222_RX") (pin "C") (pinfunction "C_C") (pintype "passive"))
      (node (ref "R17") (pin "2") (pinfunction "2_2") (pintype "passive"))
      (node (ref "STM32F103RET6") (pin "43") (pinfunction "PA10_43") (pintype "bidirectional"))
    )
    (net (code "74") (name "USART1_TX") (class "Default")
      (node (ref "R12") (pin "2") (pinfunction "2_2") (pintype "passive"))
      (node (ref "STM32F103RET6") (pin "42") (pinfunction "PA9_42") (pintype "bidirectional"))
    )
    (net (code "75") (name "USART3_RX") (class "Default")
      (node (ref "STM32F103RET6") (pin "52") (pinfunction "PC11_52") (pintype "bidirectional"))
    )
    (net (code "76") (name "USART3_TX") (class "Default")
      (node (ref "2N2222_TX1") (pin "B") (pinfunction "B_B") (pintype "passive"))
      (node (ref "STM32F103RET6") (pin "51") (pinfunction "PC10_51") (pintype "bidirectional"))
    )
    (net (code "77") (name "V+") (class "Default")
      (node (ref "BAT60JFILM") (pin "A") (pinfunction "A_A") (pintype "passive"))
      (node (ref "C20") (pin "1") (pinfunction "1_1") (pintype "passive"))
      (node (ref "C21") (pin "1") (pinfunction "1_1") (pintype "passive"))
      (node (ref "C22") (pin "1") (pinfunction "1_1") (pintype "passive"))
      (node (ref "C5") (pin "+") (pinfunction "+_+") (pintype "passive"))
      (node (ref "C7") (pin "1") (pinfunction "1_1") (pintype "passive"))
      (node (ref "CH0") (pin "2") (pinfunction "2_2") (pintype "passive"))
      (node (ref "CH1") (pin "2") (pinfunction "2_2") (pintype "passive"))
      (node (ref "CH10") (pin "2") (pinfunction "2_2") (pintype "passive"))
      (node (ref "CH11") (pin "2") (pinfunction "2_2") (pintype "passive"))
      (node (ref "CH2") (pin "2") (pinfunction "2_2") (pintype "passive"))
      (node (ref "CH3") (pin "2") (pinfunction "2_2") (pintype "passive"))
      (node (ref "CH4") (pin "2") (pinfunction "2_2") (pintype "passive"))
      (node (ref "CH5") (pin "2") (pinfunction "2_2") (pintype "passive"))
      (node (ref "CH6") (pin "2") (pinfunction "2_2") (pintype "passive"))
      (node (ref "CH7") (pin "2") (pinfunction "2_2") (pintype "passive"))
      (node (ref "CH8") (pin "2") (pinfunction "2_2") (pintype "passive"))
      (node (ref "CH9") (pin "2") (pinfunction "2_2") (pintype "passive"))
      (node (ref "SBUS") (pin "2") (pinfunction "2_2") (pintype "passive"))
      (node (ref "SPORT") (pin "2") (pinfunction "2_2") (pintype "passive"))
    )
    (net (code "78") (name "VCC") (class "Default")
      (node (ref "C10") (pin "1") (pinfunction "1_1") (pintype "passive"))
      (node (ref "C11") (pin "1") (pinfunction "1_1") (pintype "passive"))
      (node (ref "C12") (pin "1") (pinfunction "1_1") (pintype "passive"))
      (node (ref "C13") (pin "1") (pinfunction "1_1") (pintype "passive"))
      (node (ref "C14") (pin "1") (pinfunction "1_1") (pintype "passive"))
      (node (ref "C15") (pin "1") (pinfunction "1_1") (pintype "passive"))
      (node (ref "C16") (pin "1") (pinfunction "1_1") (pintype "passive"))
      (node (ref "C17") (pin "1") (pinfunction "1_1") (pintype "passive"))
      (node (ref "C18") (pin "1") (pinfunction "1_1") (pintype "passive"))
      (node (ref "C25") (pin "1") (pinfunction "1_1") (pintype "passive"))
      (node (ref "C3") (pin "1") (pinfunction "1_1") (pintype "passive"))
      (node (ref "C4") (pin "2") (pinfunction "2_2") (pintype "passive"))
      (node (ref "C6") (pin "1") (pinfunction "1_1") (pintype "passive"))
      (node (ref "FCM1608-0603") (pin "1") (pinfunction "P$1_1") (pintype "bidirectional"))
      (node (ref "IC1") (pin "2") (pinfunction "VOUT_2") (pintype "power_in"))
      (node (ref "IC1") (pin "4") (pinfunction "VOUT_4") (pintype "power_in"))
      (node (ref "MPU9150") (pin "13") (pinfunction "VDD_13") (pintype "bidirectional"))
      (node (ref "MPU9150") (pin "3") (pinfunction "VDD_3") (pintype "bidirectional"))
      (node (ref "MPU9150") (pin "8") (pinfunction "VLOGIC_8") (pintype "bidirectional"))
      (node (ref "MS5611") (pin "1") (pinfunction "VDD_1") (pintype "power_in"))
      (node (ref "MS5611") (pin "2") (pinfunction "PS_2") (pintype "input"))
      (node (ref "NRF24L01_SMD") (pin "P$8") (pinfunction "VDD_P$8") (pintype "bidirectional"))
      (node (ref "R10") (pin "1") (pinfunction "1_1") (pintype "passive"))
      (node (ref "R11") (pin "2") (pinfunction "2_2") (pintype "passive"))
      (node (ref "R17") (pin "1") (pinfunction "1_1") (pintype "passive"))
      (node (ref "R18") (pin "1") (pinfunction "1_1") (pintype "passive"))
      (node (ref "R20") (pin "2") (pinfunction "2_2") (pintype "passive"))
      (node (ref "R22") (pin "1") (pinfunction "1_1") (pintype "passive"))
      (node (ref "R3") (pin "1") (pinfunction "1_1") (pintype "passive"))
      (node (ref "R39") (pin "1") (pinfunction "1_1") (pintype "passive"))
      (node (ref "R40") (pin "2") (pinfunction "2_2") (pintype "passive"))
      (node (ref "R9") (pin "1") (pinfunction "1_1") (pintype "passive"))
      (node (ref "RFM95") (pin "13") (pinfunction "VCC_13") (pintype "bidirectional"))
      (node (ref "STM32F103RET6") (pin "1") (pinfunction "VBAT_1") (pintype "power_in"))
      (node (ref "STM32F103RET6") (pin "19") (pinfunction "VDD_4_19") (pintype "power_in"))
      (node (ref "STM32F103RET6") (pin "32") (pinfunction "VDD_1_32") (pintype "power_in"))
      (node (ref "STM32F103RET6") (pin "48") (pinfunction "VDD_2_48") (pintype "power_in"))
      (node (ref "STM32F103RET6") (pin "64") (pinfunction "VDD_3_64") (pintype "power_in"))
      (node (ref "SWD") (pin "1") (pinfunction "1_1") (pintype "passive"))
    )
    (net (code "79") (name "VDD") (class "Default")
      (node (ref "BAT60JFILM") (pin "C") (pinfunction "C_C") (pintype "passive"))
      (node (ref "IC1") (pin "3") (pinfunction "VIN_3") (pintype "input"))
    )
    (net (code "80") (name "unconnected-(MPU9150-CLKOUT-Pad22)") (class "Default")
      (node (ref "MPU9150") (pin "22") (pinfunction "CLKOUT_22") (pintype "bidirectional"))
    )
    (net (code "81") (name "unconnected-(MS5611-SDO-Pad6)") (class "Default")
      (node (ref "MS5611") (pin "6") (pinfunction "SDO_6") (pintype "output"))
    )
    (net (code "82") (name "unconnected-(STM32F103RET6C-PA4-Pad20)") (class "Default")
      (node (ref "STM32F103RET6") (pin "20") (pinfunction "PA4_20") (pintype "bidirectional"))
    )
    (net (code "83") (name "unconnected-(STM32F103RET6E-PB3-Pad55)") (class "Default")
      (node (ref "STM32F103RET6") (pin "55") (pinfunction "PB3_55") (pintype "bidirectional"))
    )
    (net (code "84") (name "unconnected-(STM32F103RET6F-PC13-Pad2)") (class "Default")
      (node (ref "STM32F103RET6") (pin "2") (pinfunction "PC13_2") (pintype "bidirectional"))
    )
    (net (code "85") (name "unconnected-(STM32F103RET6F-PC14-Pad3)") (class "Default")
      (node (ref "STM32F103RET6") (pin "3") (pinfunction "PC14_3") (pintype "bidirectional"))
    )
    (net (code "86") (name "unconnected-(STM32F103RET6F-PC15-Pad4)") (class "Default")
      (node (ref "STM32F103RET6") (pin "4") (pinfunction "PC15_4") (pintype "bidirectional"))
    )
    (net (code "87") (name "unconnected-(STM32F103RET6H-PD2-Pad54)") (class "Default")
      (node (ref "STM32F103RET6") (pin "54") (pinfunction "PD2_54") (pintype "bidirectional"))
    )
  )
)
